# Grabber_DIOT_TOP.net
KiCad netlist of a schematic drawn in Altium Designer
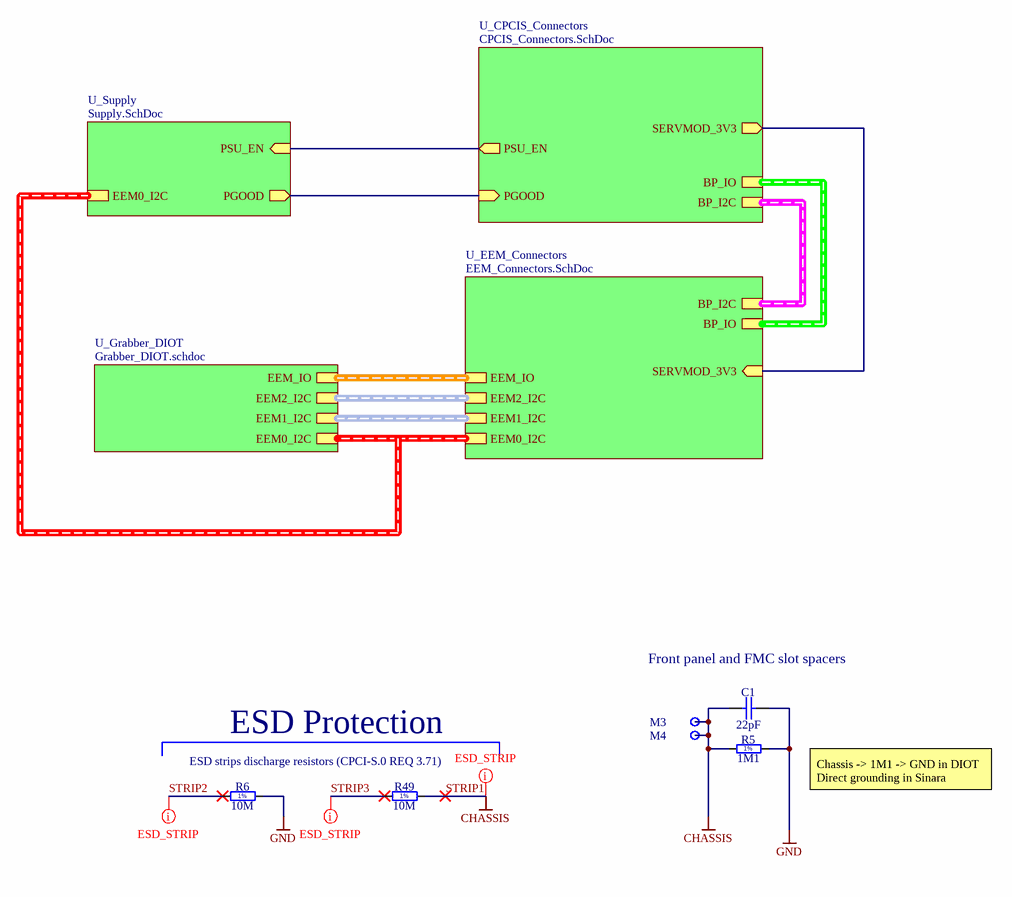
[diagram p0: Grabber_DIOT_TOP.SchDoc]

(export (version "E")
  (design (tool "Eeschema 10.0.6"))
  (components
    (comp (ref "C1")
      (value "22pF")
      (footprint "CAPC1005X55N")
      (description "Non-polarised capacitor")
      (fields
        (field (name "PART NUMBER") "CC0402_22PF_50V_5%_C0G")
        (field (name "VOLTAGE") "50V")
        (field (name "AUTHOR") "CERN DEM JLC")
      )
      (libsource (lib "Capacitors") (part "Capacitor - non polarized"))
    )
    (comp (ref "M3")
      (value "Plated Hole")
      (footprint "MTG300_600")
      (description "Single Terminal Socket")
      (fields (field (name "PART NUMBER") "PLATED_HOLE3.0_PAD6.0") (field (name "AUTHOR") "CERN DEM JLC"))
      (libsource (lib "Eletro-mechanical") (part "Single Terminal Socket"))
    )
    (comp (ref "M4")
      (value "Plated Hole")
      (footprint "MTG300_600")
      (description "Single Terminal Socket")
      (fields (field (name "PART NUMBER") "PLATED_HOLE3.0_PAD6.0") (field (name "AUTHOR") "CERN DEM JLC"))
      (libsource (lib "Eletro-mechanical") (part "Single Terminal Socket"))
    )
    (comp (ref "R5")
      (value "1M1")
      (footprint "RESC2012X60N")
      (description "Resistor - 1%")
      (fields
        (field (name "PART NUMBER") "R0805_1M1_1%_0.125W_100PPM")
        (field (name "MANUFACTURER") "GENERIC")
        (field (name "AUTHOR") "CERN DEM JLC")
      )
      (libsource (lib "Resistors") (part "Resistor - 1%"))
    )
    (comp (ref "R6")
      (value "10M")
      (footprint "RESC2113X55N")
      (description "150V, Standard Thick Film Chip Resistor")
      (fields
        (field (name "PART NUMBER") "R0805_10M_1%_0.125W_100PPM")
        (field (name "POWER") "0.125W")
        (field (name "AUTHOR") "CERN DEM BC")
      )
      (libsource (lib "Resistors") (part "Resistor - 1%"))
    )
    (comp (ref "R49")
      (value "10M")
      (footprint "RESC2113X55N")
      (description "150V, Standard Thick Film Chip Resistor")
      (fields
        (field (name "PART NUMBER") "R0805_10M_1%_0.125W_100PPM")
        (field (name "POWER") "0.125W")
        (field (name "AUTHOR") "CERN DEM BC")
      )
      (libsource (lib "Resistors") (part "Resistor - 1%"))
    )
  )
  (nets
    (net (code "11") (name "/STRIP2") (class "Default")
      (node (ref "R6") (pin "1") (pinfunction "1_1") (pintype "passive+no_connect"))
    )
    (net (code "12") (name "/STRIP3") (class "Default")
      (node (ref "R49") (pin "1") (pinfunction "1_1") (pintype "passive+no_connect"))
    )
    (net (code "13") (name "CHASSIS") (class "Default")
      (node (ref "C1") (pin "1") (pinfunction "1_1") (pintype "passive"))
      (node (ref "M3") (pin "1") (pinfunction "1_1") (pintype "bidirectional"))
      (node (ref "M4") (pin "1") (pinfunction "1_1") (pintype "bidirectional"))
      (node (ref "R49") (pin "2") (pinfunction "2_2") (pintype "passive"))
      (node (ref "R5") (pin "1") (pinfunction "1_1") (pintype "passive"))
    )
    (net (code "14") (name "GND") (class "Default")
      (node (ref "C1") (pin "2") (pinfunction "2_2") (pintype "passive"))
      (node (ref "R5") (pin "2") (pinfunction "2_2") (pintype "passive"))
      (node (ref "R6") (pin "2") (pinfunction "2_2") (pintype "passive"))
    )
  )
)
